# top.net
KiCad netlist of a schematic drawn in EAGLE
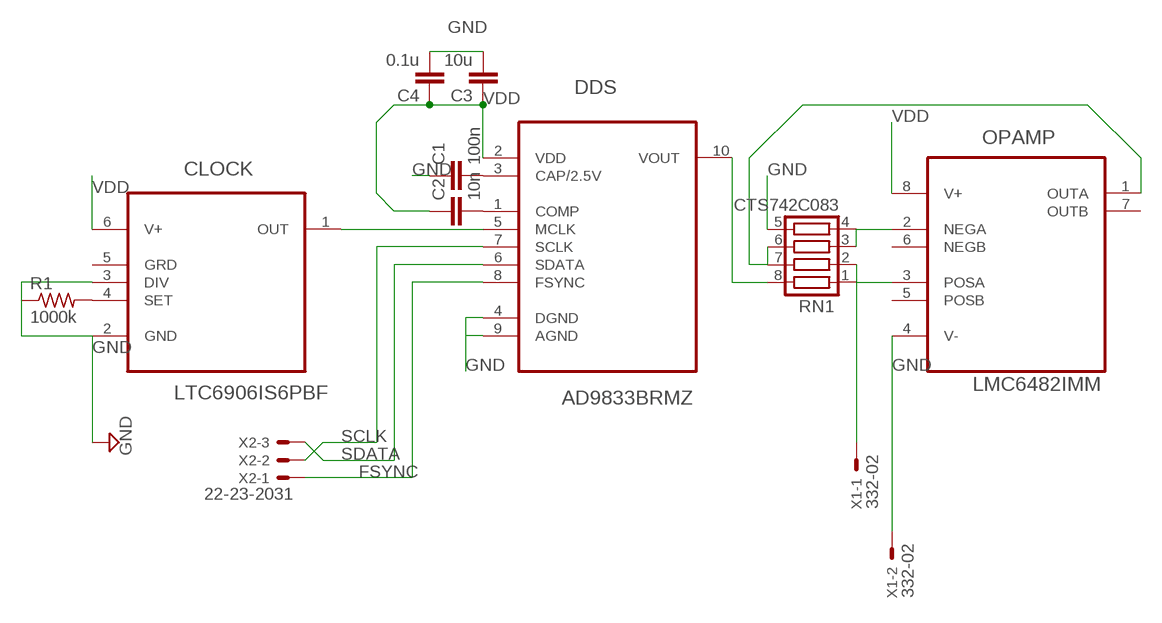
[diagram p0: schematic, sheet 1]

(export (version "E")
  (design (tool "Eeschema 10.0.6"))
  (components
    (comp (ref "C1")
      (value "100n")
      (footprint "eagle-import:C0805")
      (libsource (lib "eagle-import") (part "C-EUC0805"))
    )
    (comp (ref "C2")
      (value "10n")
      (footprint "eagle-import:C0805")
      (libsource (lib "eagle-import") (part "C-EUC0805"))
    )
    (comp (ref "C3")
      (value "10u")
      (footprint "eagle-import:C0805")
      (libsource (lib "eagle-import") (part "C-EUC0805"))
    )
    (comp (ref "C4")
      (value "0.1u")
      (footprint "eagle-import:C0805")
      (libsource (lib "eagle-import") (part "C-EUC0805"))
    )
    (comp (ref "CLOCK")
      (value "LTC6906IS6PBF")
      (footprint "eagle-import:SOT95P280X100-6N")
      (fields (field (name "MPN") "LTC6906IS6#PBF"))
      (libsource (lib "eagle-import") (part "LTC6906IS6PBF"))
    )
    (comp (ref "DDS")
      (value "AD9833BRMZ")
      (footprint "eagle-import:SOP50P490X110-10N")
      (libsource (lib "eagle-import") (part "AD9833BRMZ"))
    )
    (comp (ref "OPAMP")
      (value "LMC6482IMM")
      (footprint "eagle-import:SOP65P490X109-8N")
      (libsource (lib "eagle-import") (part "LMC6482IMM"))
    )
    (comp (ref "R1")
      (value "1000k")
      (footprint "eagle-import:M0805")
      (libsource (lib "eagle-import") (part "R-US_M0805"))
    )
    (comp (ref "RN1")
      (value "CTS742C083")
      (footprint "eagle-import:CTS742C083")
      (libsource (lib "eagle-import") (part "CTS742C083"))
    )
    (comp (ref "X1")
      (value "332-02")
      (footprint "eagle-import:332-02")
      (libsource (lib "eagle-import") (part "332-02"))
    )
    (comp (ref "X2")
      (value "22-23-2031")
      (footprint "eagle-import:22-23-2031")
      (fields (field (name "MF") "MOLEX"))
      (libsource (lib "eagle-import") (part "22-23-2031"))
    )
  )
  (nets
    (net (code "1") (name "/FSYNC") (class "Default")
      (node (ref "DDS") (pin "8") (pinfunction "FSYNC_8") (pintype "input"))
      (node (ref "X2") (pin "1") (pinfunction "S_1") (pintype "passive"))
    )
    (net (code "2") (name "/SCLK") (class "Default")
      (node (ref "DDS") (pin "7") (pinfunction "SCLK_7") (pintype "input"))
      (node (ref "X2") (pin "2") (pinfunction "S_2") (pintype "passive"))
    )
    (net (code "3") (name "/SDATA") (class "Default")
      (node (ref "DDS") (pin "6") (pinfunction "SDATA_6") (pintype "input"))
      (node (ref "X2") (pin "3") (pinfunction "S_3") (pintype "passive"))
    )
    (net (code "4") (name "/VDD") (class "Default")
      (node (ref "C2") (pin "1") (pinfunction "1_1") (pintype "passive"))
      (node (ref "C3") (pin "1") (pinfunction "1_1") (pintype "passive"))
      (node (ref "C4") (pin "1") (pinfunction "1_1") (pintype "passive"))
      (node (ref "CLOCK") (pin "6") (pinfunction "V+_6") (pintype "power_in"))
      (node (ref "DDS") (pin "2") (pinfunction "VDD_2") (pintype "power_in"))
      (node (ref "OPAMP") (pin "8") (pinfunction "V+_8") (pintype "power_in"))
    )
    (net (code "5") (name "GND") (class "Default")
      (node (ref "C1") (pin "1") (pinfunction "1_1") (pintype "passive"))
      (node (ref "C3") (pin "2") (pinfunction "2_2") (pintype "passive"))
      (node (ref "C4") (pin "2") (pinfunction "2_2") (pintype "passive"))
      (node (ref "CLOCK") (pin "2") (pinfunction "GND_2") (pintype "passive"))
      (node (ref "CLOCK") (pin "3") (pinfunction "DIV_3") (pintype "input"))
      (node (ref "DDS") (pin "4") (pinfunction "DGND_4") (pintype "passive"))
      (node (ref "DDS") (pin "9") (pinfunction "AGND_9") (pintype "passive"))
      (node (ref "OPAMP") (pin "4") (pinfunction "V-_4") (pintype "power_in"))
      (node (ref "R1") (pin "1") (pinfunction "1_1") (pintype "passive"))
      (node (ref "RN1") (pin "5") (pinfunction "5_5") (pintype "passive"))
      (node (ref "X1") (pin "2") (pinfunction "S_2") (pintype "passive"))
    )
    (net (code "6") (name "Net-(CLOCK-OUT)") (class "Default")
      (node (ref "CLOCK") (pin "1") (pinfunction "OUT_1") (pintype "output"))
      (node (ref "DDS") (pin "5") (pinfunction "MCLK_5") (pintype "input"))
    )
    (net (code "7") (name "Net-(CLOCK-SET)") (class "Default")
      (node (ref "CLOCK") (pin "4") (pinfunction "SET_4") (pintype "input"))
      (node (ref "R1") (pin "2") (pinfunction "2_2") (pintype "passive"))
    )
    (net (code "8") (name "Net-(DDS-CAP{slash}2.5V)") (class "Default")
      (node (ref "C1") (pin "2") (pinfunction "2_2") (pintype "passive"))
      (node (ref "DDS") (pin "3") (pinfunction "CAP/2.5V_3") (pintype "passive"))
    )
    (net (code "9") (name "Net-(DDS-COMP)") (class "Default")
      (node (ref "C2") (pin "2") (pinfunction "2_2") (pintype "passive"))
      (node (ref "DDS") (pin "1") (pinfunction "COMP_1") (pintype "passive"))
    )
    (net (code "10") (name "Net-(DDS-VOUT)") (class "Default")
      (node (ref "DDS") (pin "10") (pinfunction "VOUT_10") (pintype "output"))
      (node (ref "RN1") (pin "8") (pinfunction "8_8") (pintype "passive"))
    )
    (net (code "11") (name "Net-(OPAMP-NEGA)") (class "Default")
      (node (ref "OPAMP") (pin "2") (pinfunction "NEGA_2") (pintype "input"))
      (node (ref "RN1") (pin "3") (pinfunction "3_3") (pintype "passive"))
      (node (ref "RN1") (pin "4") (pinfunction "4_4") (pintype "passive"))
    )
    (net (code "12") (name "Net-(OPAMP-OUTA)") (class "Default")
      (node (ref "OPAMP") (pin "1") (pinfunction "OUTA_1") (pintype "output"))
      (node (ref "RN1") (pin "6") (pinfunction "6_6") (pintype "passive"))
      (node (ref "RN1") (pin "7") (pinfunction "7_7") (pintype "passive"))
    )
    (net (code "13") (name "Net-(OPAMP-POSA)") (class "Default")
      (node (ref "OPAMP") (pin "3") (pinfunction "POSA_3") (pintype "input"))
      (node (ref "RN1") (pin "1") (pinfunction "1_1") (pintype "passive"))
      (node (ref "RN1") (pin "2") (pinfunction "2_2") (pintype "passive"))
      (node (ref "X1") (pin "1") (pinfunction "S_1") (pintype "passive"))
    )
    (net (code "14") (name "unconnected-(CLOCK-GRD-Pad5)") (class "Default")
      (node (ref "CLOCK") (pin "5") (pinfunction "GRD_5") (pintype "input"))
    )
    (net (code "15") (name "unconnected-(OPAMP-NEGB-Pad6)") (class "Default")
      (node (ref "OPAMP") (pin "6") (pinfunction "NEGB_6") (pintype "input"))
    )
    (net (code "16") (name "unconnected-(OPAMP-OUTB-Pad7)") (class "Default")
      (node (ref "OPAMP") (pin "7") (pinfunction "OUTB_7") (pintype "output"))
    )
    (net (code "17") (name "unconnected-(OPAMP-POSB-Pad5)") (class "Default")
      (node (ref "OPAMP") (pin "5") (pinfunction "POSB_5") (pintype "input"))
    )
  )
)
